# llrf_afe_main.net
KiCad netlist of a schematic drawn in Altium Designer
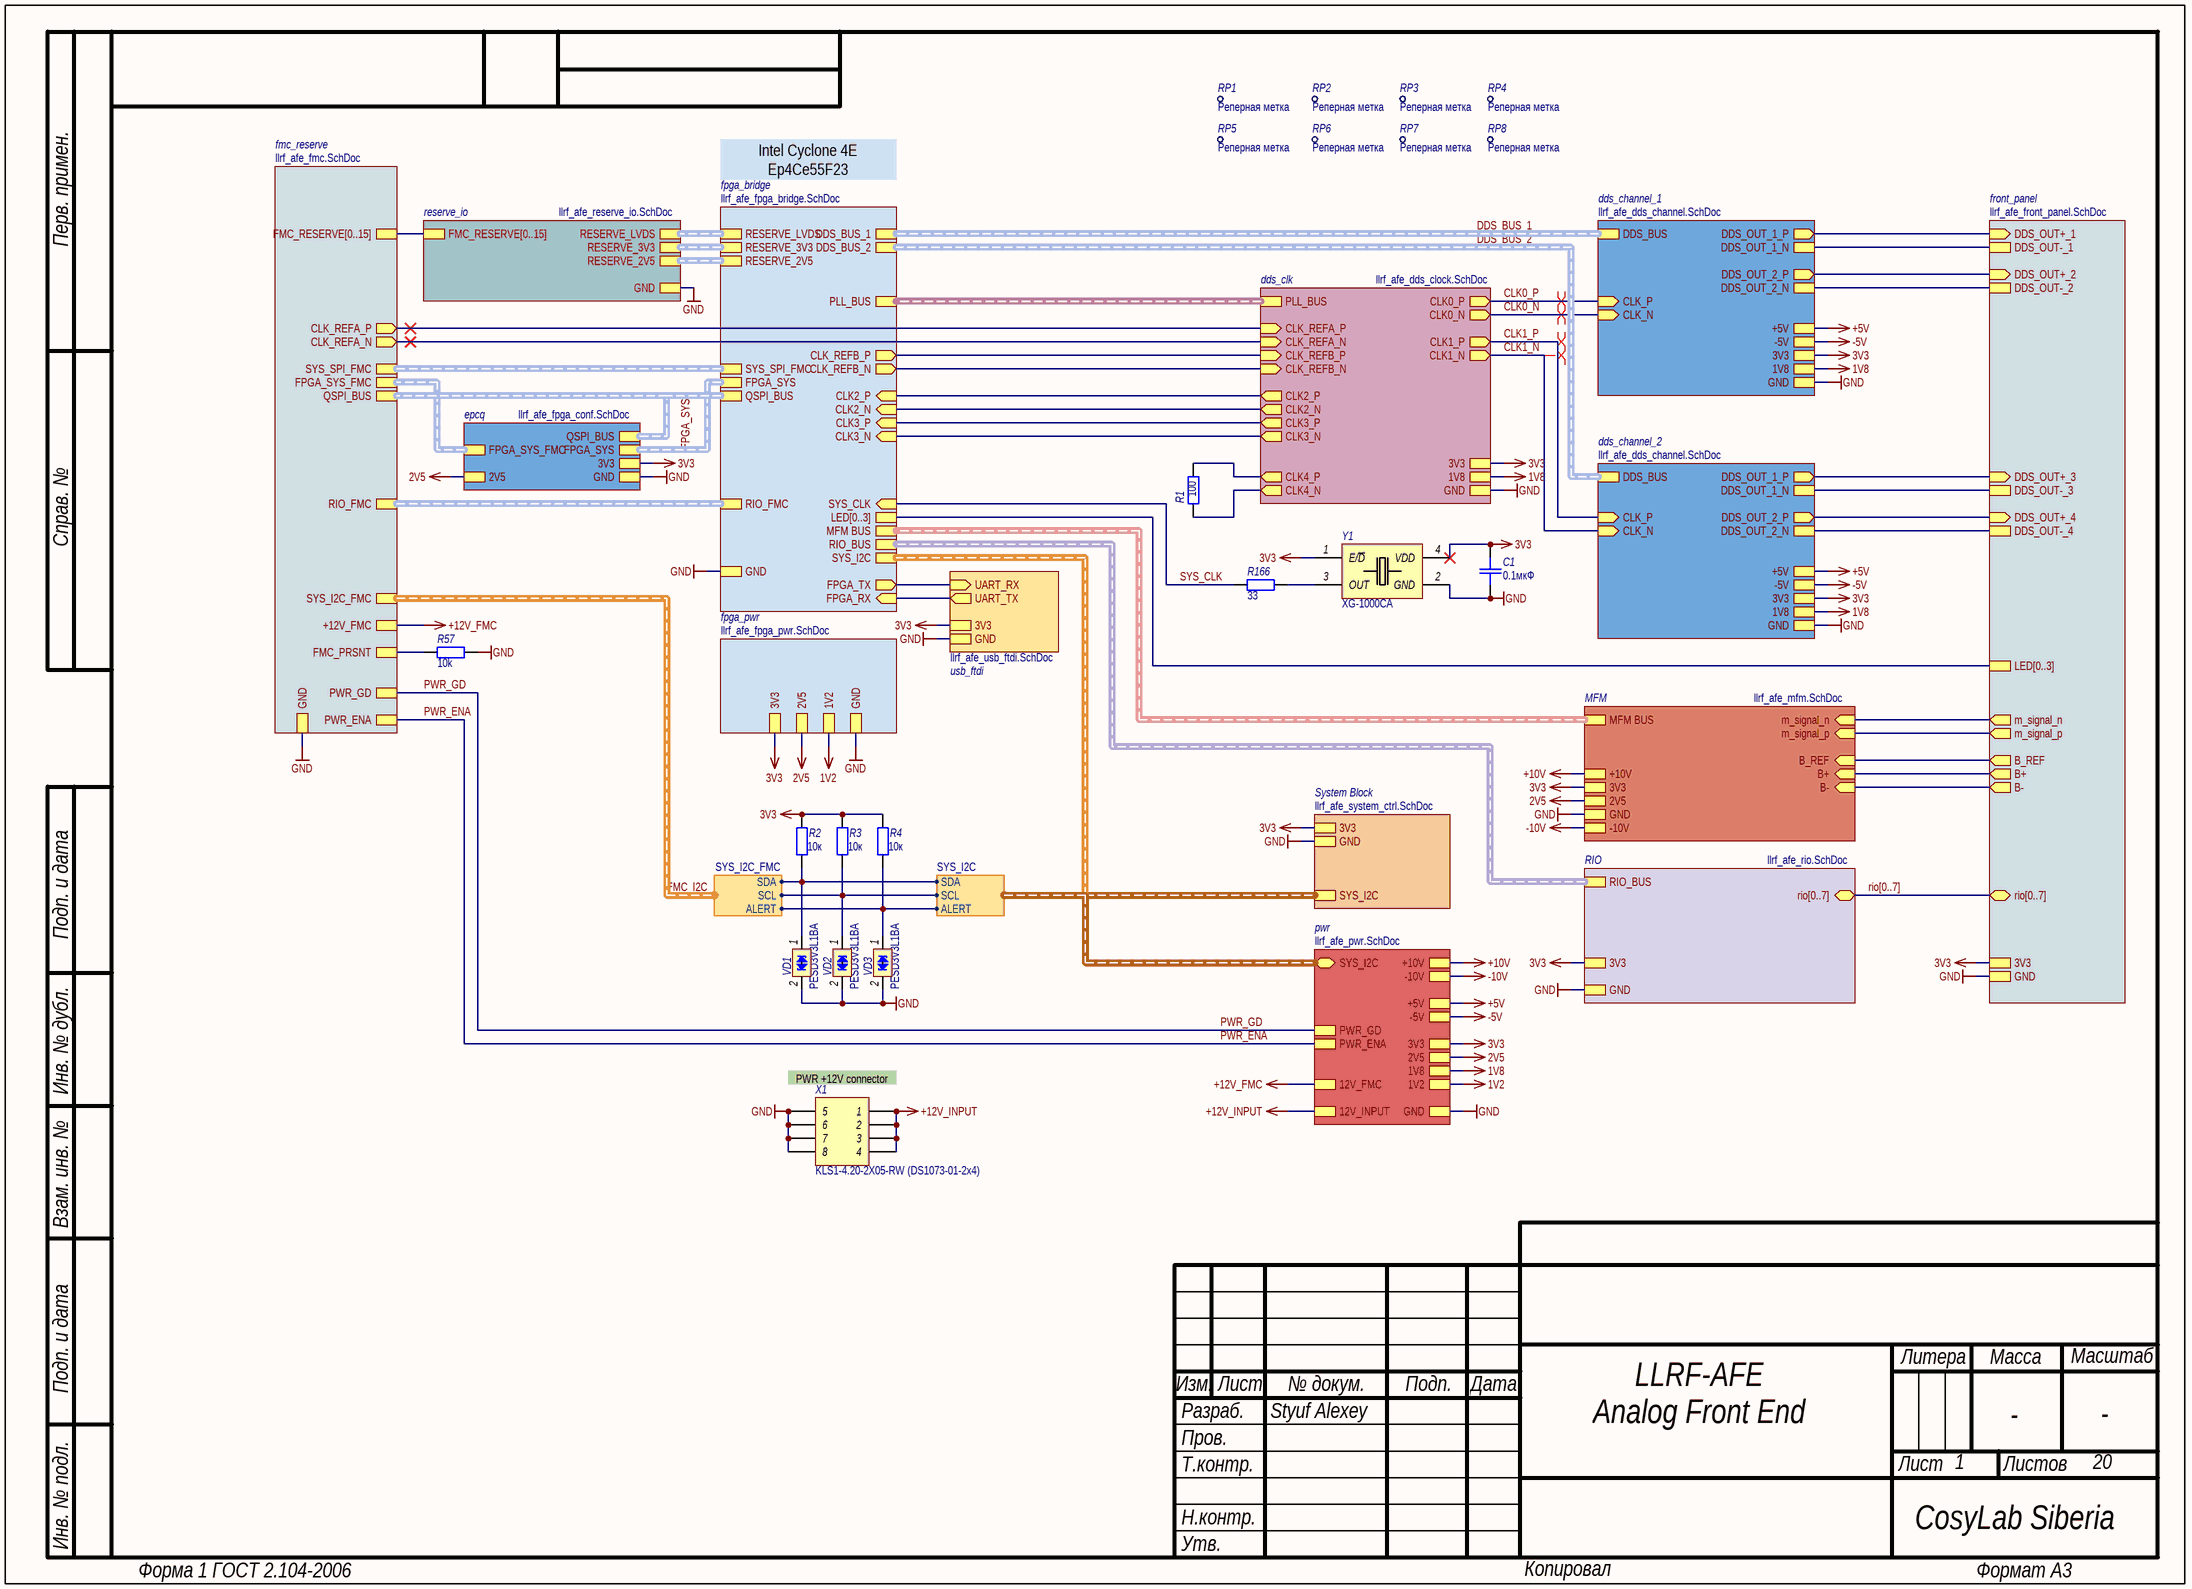
[diagram p0: llrf_afe_main.SchDoc]

(export (version "E")
  (design (tool "Eeschema 10.0.6"))
  (components
    (comp (ref "C1")
      (value "0.1мкФ")
      (footprint "SMD_C0402")
      (description "Capacitor")
      (libsource (lib "Passive") (part "Capacitor"))
    )
    (comp (ref "R1")
      (value "100")
      (footprint "SMD_0603")
      (description "Resistor")
      (libsource (lib "Passive") (part "Resistor"))
    )
    (comp (ref "R2")
      (value "10к")
      (footprint "SMD_0603")
      (description "Resistor")
      (libsource (lib "Passive") (part "Resistor"))
    )
    (comp (ref "R3")
      (value "10к")
      (footprint "SMD_0603")
      (description "Resistor")
      (libsource (lib "Passive") (part "Resistor"))
    )
    (comp (ref "R4")
      (value "10к")
      (footprint "SMD_0603")
      (description "Resistor")
      (libsource (lib "Passive") (part "Resistor"))
    )
    (comp (ref "R57")
      (value "10k")
      (footprint "SMD_0603")
      (description "Resistor")
      (libsource (lib "") (part "Resistor_1"))
    )
    (comp (ref "R166")
      (value "33")
      (footprint "SMD_0603")
      (description "Resistor")
      (libsource (lib "") (part "Resistor_1"))
    )
    (comp (ref "RP1")
      (value "RP")
      (footprint "ReperPoint")
      (fields (field (name "НАИМЕНОВАНИЕ") "Реперная метка"))
      (libsource (lib "Connector") (part "RP"))
    )
    (comp (ref "RP2")
      (value "RP")
      (footprint "ReperPoint")
      (fields (field (name "НАИМЕНОВАНИЕ") "Реперная метка"))
      (libsource (lib "Connector") (part "RP"))
    )
    (comp (ref "RP3")
      (value "RP")
      (footprint "ReperPoint")
      (fields (field (name "НАИМЕНОВАНИЕ") "Реперная метка"))
      (libsource (lib "Connector") (part "RP"))
    )
    (comp (ref "RP4")
      (value "RP")
      (footprint "ReperPoint")
      (fields (field (name "НАИМЕНОВАНИЕ") "Реперная метка"))
      (libsource (lib "Connector") (part "RP"))
    )
    (comp (ref "RP5")
      (value "RP")
      (footprint "ReperPoint")
      (fields (field (name "НАИМЕНОВАНИЕ") "Реперная метка"))
      (libsource (lib "Connector") (part "RP"))
    )
    (comp (ref "RP6")
      (value "RP")
      (footprint "ReperPoint")
      (fields (field (name "НАИМЕНОВАНИЕ") "Реперная метка"))
      (libsource (lib "Connector") (part "RP"))
    )
    (comp (ref "RP7")
      (value "RP")
      (footprint "ReperPoint")
      (fields (field (name "НАИМЕНОВАНИЕ") "Реперная метка"))
      (libsource (lib "Connector") (part "RP"))
    )
    (comp (ref "RP8")
      (value "RP")
      (footprint "ReperPoint")
      (fields (field (name "НАИМЕНОВАНИЕ") "Реперная метка"))
      (libsource (lib "Connector") (part "RP"))
    )
    (comp (ref "VD1")
      (value "PESD3V3")
      (footprint "SOD-323")
      (description "Low capacitance bidirectional ESD protection diodes")
      (fields (field (name "НАИМЕНОВАНИЕ") "PESD3V3L1BA"))
      (libsource (lib "PESDxL1BA") (part "PESDxL1BA"))
    )
    (comp (ref "VD2")
      (value "PESD3V3")
      (footprint "SOD-323")
      (description "Low capacitance bidirectional ESD protection diodes")
      (fields (field (name "НАИМЕНОВАНИЕ") "PESD3V3L1BA"))
      (libsource (lib "PESDxL1BA") (part "PESDxL1BA"))
    )
    (comp (ref "VD3")
      (value "PESD3V3")
      (footprint "SOD-323")
      (description "Low capacitance bidirectional ESD protection diodes")
      (fields (field (name "НАИМЕНОВАНИЕ") "PESD3V3L1BA"))
      (libsource (lib "PESDxL1BA") (part "PESDxL1BA"))
    )
    (comp (ref "X1")
      (value "KLS1-4.20-2X05-R (DS1073-01-2x4)")
      (footprint "KLS1-4.20-2X04")
      (description "Вилка на плату угловая 4.2мм 8pin со втулками (дополнительное питание PCIe)")
      (fields (field (name "НАИМЕНОВАНИЕ") "KLS1-4.20-2X05-RW (DS1073-01-2x4)"))
      (libsource (lib "Connector") (part "KLS1-4.20-2X05-R"))
    )
    (comp (ref "Y1")
      (value "XG-1000CA")
      (footprint "SMD_7050_Crystal_Oscillator")
      (description "Crystall oscillator, CMOS, 3.3V, SMD7050")
      (fields (field (name "НАИМЕНОВАНИЕ") "XG-1000CA"))
      (libsource (lib "Oscillator") (part "Crystal_Oscillator"))
    )
  )
  (nets
    (net (code "17") (name "+12V_INPUT") (class "Default")
      (node (ref "X1") (pin "1") (pinfunction "1_1") (pintype "passive"))
      (node (ref "X1") (pin "2") (pinfunction "2_2") (pintype "passive"))
      (node (ref "X1") (pin "3") (pinfunction "3_3") (pintype "passive"))
      (node (ref "X1") (pin "4") (pinfunction "4_4") (pintype "passive"))
    )
    (net (code "31") (name "/CLK4_N") (class "Default")
      (node (ref "R1") (pin "1") (pinfunction "1_1") (pintype "passive"))
    )
    (net (code "32") (name "/CLK4_P") (class "Default")
      (node (ref "R1") (pin "2") (pinfunction "2_2") (pintype "passive"))
    )
    (net (code "46") (name "/FMC_PRSNT") (class "Default")
      (node (ref "R57") (pin "2") (pinfunction "2_2") (pintype "passive"))
    )
    (net (code "61") (name "/SYS_CLK") (class "Default")
      (node (ref "R166") (pin "2") (pinfunction "2_2") (pintype "passive"))
    )
    (net (code "74") (name "3V3") (class "Default")
      (node (ref "C1") (pin "2") (pinfunction "2_2") (pintype "passive"))
      (node (ref "R2") (pin "2") (pinfunction "2_2") (pintype "passive"))
      (node (ref "R3") (pin "2") (pinfunction "2_2") (pintype "passive"))
      (node (ref "R4") (pin "2") (pinfunction "2_2") (pintype "passive"))
      (node (ref "Y1") (pin "1") (pinfunction "E/~{D}_1") (pintype "passive"))
      (node (ref "Y1") (pin "4") (pinfunction "VDD_4") (pintype "passive"))
    )
    (net (code "75") (name "GND") (class "Default")
      (node (ref "C1") (pin "1") (pinfunction "1_1") (pintype "passive"))
      (node (ref "R57") (pin "1") (pinfunction "1_1") (pintype "passive"))
      (node (ref "VD1") (pin "2") (pinfunction "cathode_2_2") (pintype "passive"))
      (node (ref "VD2") (pin "2") (pinfunction "cathode_2_2") (pintype "passive"))
      (node (ref "VD3") (pin "2") (pinfunction "cathode_2_2") (pintype "passive"))
      (node (ref "X1") (pin "5") (pinfunction "5_5") (pintype "passive"))
      (node (ref "X1") (pin "6") (pinfunction "6_6") (pintype "passive"))
      (node (ref "X1") (pin "7") (pinfunction "7_7") (pintype "passive"))
      (node (ref "X1") (pin "8") (pinfunction "8_8") (pintype "passive"))
      (node (ref "Y1") (pin "2") (pinfunction "GND_2") (pintype "passive"))
    )
    (net (code "76") (name "Net-(VD1-cathode_1)") (class "Default")
      (node (ref "R2") (pin "1") (pinfunction "1_1") (pintype "passive"))
      (node (ref "VD1") (pin "1") (pinfunction "cathode_1_1") (pintype "passive"))
    )
    (net (code "77") (name "Net-(VD2-cathode_1)") (class "Default")
      (node (ref "R3") (pin "1") (pinfunction "1_1") (pintype "passive"))
      (node (ref "VD2") (pin "1") (pinfunction "cathode_1_1") (pintype "passive"))
    )
    (net (code "78") (name "Net-(VD3-cathode_1)") (class "Default")
      (node (ref "R4") (pin "1") (pinfunction "1_1") (pintype "passive"))
      (node (ref "VD3") (pin "1") (pinfunction "cathode_1_1") (pintype "passive"))
    )
    (net (code "79") (name "Net-(Y1-OUT)") (class "Default")
      (node (ref "R166") (pin "1") (pinfunction "1_1") (pintype "passive"))
      (node (ref "Y1") (pin "3") (pinfunction "OUT_3") (pintype "passive"))
    )
  )
)
